# 05_MPU6500.net
KiCad netlist of a schematic drawn in Altium Designer
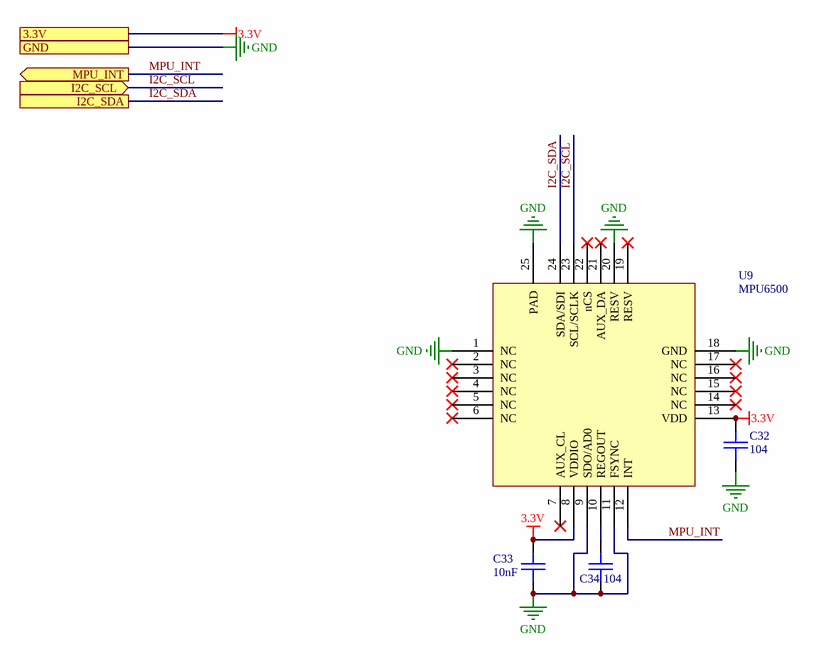
[diagram p0: 05_MPU6500.SchDoc]

(export (version "E")
  (design (tool "Eeschema 10.0.6"))
  (components
    (comp (ref "C32")
      (value "104")
      (footprint "0402C")
      (description "电容")
      (libsource (lib "MY_Schlib") (part "CAP"))
    )
    (comp (ref "C33")
      (value "10nF")
      (footprint "0402C")
      (description "电容")
      (libsource (lib "MY_Schlib") (part "CAP"))
    )
    (comp (ref "C34")
      (value "104")
      (footprint "0402C")
      (description "电容")
      (libsource (lib "MY_Schlib") (part "CAP"))
    )
    (comp (ref "U9")
      (value "MPU6500")
      (footprint "QFN-24_L3.0-W3.0-P0.40-BL-EP")
      (description "三轴加速度计和三轴陀螺仪")
      (libsource (lib "MY_Schlib") (part "MPU6500"))
    )
  )
  (nets
    (net (code "1") (name "/I2C_SCL") (class "Default")
      (node (ref "U9") (pin "23") (pinfunction "SCL/SCLK_23") (pintype "passive"))
    )
    (net (code "2") (name "/I2C_SDA") (class "Default")
      (node (ref "U9") (pin "24") (pinfunction "SDA/SDI_24") (pintype "passive"))
    )
    (net (code "3") (name "/MPU_INT") (class "Default")
      (node (ref "U9") (pin "12") (pinfunction "INT_12") (pintype "passive"))
    )
    (net (code "4") (name "3.3V") (class "Default")
      (node (ref "C32") (pin "1") (pinfunction "1_1") (pintype "passive"))
      (node (ref "C33") (pin "2") (pinfunction "2_2") (pintype "passive"))
      (node (ref "U9") (pin "13") (pinfunction "VDD_13") (pintype "passive"))
      (node (ref "U9") (pin "8") (pinfunction "VDDIO_8") (pintype "passive"))
    )
    (net (code "5") (name "GND") (class "Default")
      (node (ref "C32") (pin "2") (pinfunction "2_2") (pintype "passive"))
      (node (ref "C33") (pin "1") (pinfunction "1_1") (pintype "passive"))
      (node (ref "C34") (pin "2") (pinfunction "2_2") (pintype "passive"))
      (node (ref "U9") (pin "1") (pinfunction "NC_1") (pintype "passive"))
      (node (ref "U9") (pin "11") (pinfunction "FSYNC_11") (pintype "passive"))
      (node (ref "U9") (pin "18") (pinfunction "GND_18") (pintype "passive"))
      (node (ref "U9") (pin "20") (pinfunction "RESV_20") (pintype "passive"))
      (node (ref "U9") (pin "25") (pinfunction "PAD_25") (pintype "passive"))
      (node (ref "U9") (pin "9") (pinfunction "SDO/AD0_9") (pintype "passive"))
    )
    (net (code "6") (name "Net-(U9-REGOUT)") (class "Default")
      (node (ref "C34") (pin "1") (pinfunction "1_1") (pintype "passive"))
      (node (ref "U9") (pin "10") (pinfunction "REGOUT_10") (pintype "passive"))
    )
    (net (code "7") (name "unconnected-(U9-AUX_CL-Pad7)") (class "Default")
      (node (ref "U9") (pin "7") (pinfunction "AUX_CL_7") (pintype "passive+no_connect"))
    )
    (net (code "8") (name "unconnected-(U9-AUX_DA-Pad21)") (class "Default")
      (node (ref "U9") (pin "21") (pinfunction "AUX_DA_21") (pintype "passive+no_connect"))
    )
    (net (code "9") (name "unconnected-(U9-NC-Pad2)") (class "Default")
      (node (ref "U9") (pin "2") (pinfunction "NC_2") (pintype "passive+no_connect"))
    )
    (net (code "10") (name "unconnected-(U9-NC-Pad3)") (class "Default")
      (node (ref "U9") (pin "3") (pinfunction "NC_3") (pintype "passive+no_connect"))
    )
    (net (code "11") (name "unconnected-(U9-NC-Pad4)") (class "Default")
      (node (ref "U9") (pin "4") (pinfunction "NC_4") (pintype "passive+no_connect"))
    )
    (net (code "12") (name "unconnected-(U9-NC-Pad5)") (class "Default")
      (node (ref "U9") (pin "5") (pinfunction "NC_5") (pintype "passive+no_connect"))
    )
    (net (code "13") (name "unconnected-(U9-NC-Pad6)") (class "Default")
      (node (ref "U9") (pin "6") (pinfunction "NC_6") (pintype "passive+no_connect"))
    )
    (net (code "14") (name "unconnected-(U9-NC-Pad14)") (class "Default")
      (node (ref "U9") (pin "14") (pinfunction "NC_14") (pintype "passive+no_connect"))
    )
    (net (code "15") (name "unconnected-(U9-NC-Pad15)") (class "Default")
      (node (ref "U9") (pin "15") (pinfunction "NC_15") (pintype "passive+no_connect"))
    )
    (net (code "16") (name "unconnected-(U9-NC-Pad16)") (class "Default")
      (node (ref "U9") (pin "16") (pinfunction "NC_16") (pintype "passive+no_connect"))
    )
    (net (code "17") (name "unconnected-(U9-NC-Pad17)") (class "Default")
      (node (ref "U9") (pin "17") (pinfunction "NC_17") (pintype "passive+no_connect"))
    )
    (net (code "18") (name "unconnected-(U9-RESV-Pad19)") (class "Default")
      (node (ref "U9") (pin "19") (pinfunction "RESV_19") (pintype "passive+no_connect"))
    )
    (net (code "19") (name "unconnected-(U9-nCS-Pad22)") (class "Default")
      (node (ref "U9") (pin "22") (pinfunction "nCS_22") (pintype "passive+no_connect"))
    )
  )
)
